# bme_affect_sen_brd.net
KiCad netlist of a schematic drawn in Altium Designer
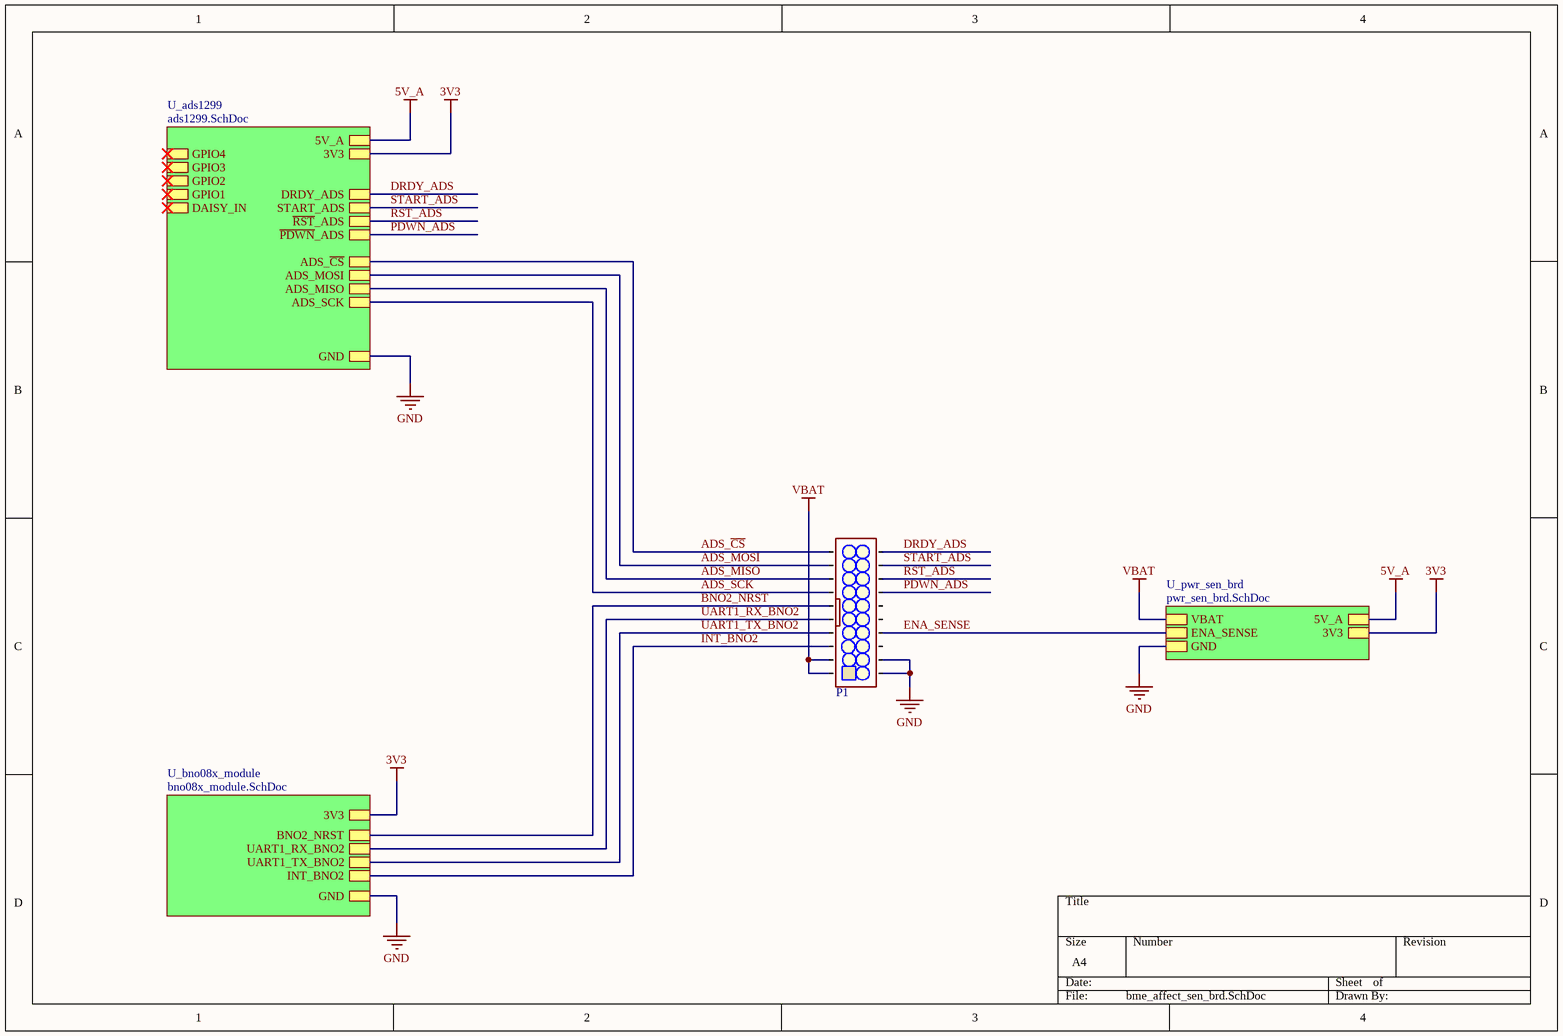
[diagram p0: bme_affect_sen_brd.SchDoc]

(export (version "E")
  (design (tool "Eeschema 10.0.6"))
  (components
    (comp (ref "P1")
      (value "2x10 Ribbon Header")
      (footprint "2x10_RIBBON_CABLE_CON")
      (description "2.54 mm")
      (fields (field (name "MANUFACTURER PART NO") "302-S201"))
      (libsource (lib "jclib") (part "2x10 Ribbon Header"))
    )
  )
  (nets
    (net (code "1") (name "/ADS_MISO") (class "Default")
      (node (ref "P1") (pin "8") (pinfunction "8_8") (pintype "passive"))
    )
    (net (code "2") (name "/ADS_MOSI") (class "Default")
      (node (ref "P1") (pin "9") (pinfunction "9_9") (pintype "passive"))
    )
    (net (code "3") (name "/ADS_SCK") (class "Default")
      (node (ref "P1") (pin "7") (pinfunction "7_7") (pintype "passive"))
    )
    (net (code "4") (name "/ADS_~{CS}") (class "Default")
      (node (ref "P1") (pin "10") (pinfunction "10_10") (pintype "passive"))
    )
    (net (code "5") (name "/BNO2_NRST") (class "Default")
      (node (ref "P1") (pin "6") (pinfunction "6_6") (pintype "passive"))
    )
    (net (code "7") (name "/DRDY_ADS") (class "Default")
      (node (ref "P1") (pin "11") (pinfunction "11_11") (pintype "passive"))
    )
    (net (code "8") (name "/ENA_SENSE") (class "Default")
      (node (ref "P1") (pin "17") (pinfunction "17_17") (pintype "passive"))
    )
    (net (code "13") (name "/INT_BNO2") (class "Default")
      (node (ref "P1") (pin "3") (pinfunction "3_3") (pintype "passive"))
    )
    (net (code "14") (name "/START_ADS") (class "Default")
      (node (ref "P1") (pin "12") (pinfunction "12_12") (pintype "passive"))
    )
    (net (code "15") (name "/UART1_RX_BNO2") (class "Default")
      (node (ref "P1") (pin "5") (pinfunction "5_5") (pintype "passive"))
    )
    (net (code "16") (name "/UART1_TX_BNO2") (class "Default")
      (node (ref "P1") (pin "4") (pinfunction "4_4") (pintype "passive"))
    )
    (net (code "17") (name "/~{PDWN}_ADS") (class "Default")
      (node (ref "P1") (pin "14") (pinfunction "14_14") (pintype "passive"))
    )
    (net (code "18") (name "/~{RST}_ADS") (class "Default")
      (node (ref "P1") (pin "13") (pinfunction "13_13") (pintype "passive"))
    )
    (net (code "21") (name "GND") (class "Default")
      (node (ref "P1") (pin "19") (pinfunction "19_19") (pintype "passive"))
      (node (ref "P1") (pin "20") (pinfunction "20_20") (pintype "passive"))
    )
    (net (code "22") (name "VBAT") (class "Default")
      (node (ref "P1") (pin "1") (pinfunction "1_1") (pintype "passive"))
      (node (ref "P1") (pin "2") (pinfunction "2_2") (pintype "passive"))
    )
    (net (code "23") (name "unconnected-(P1-Pad15)") (class "Default")
      (node (ref "P1") (pin "15") (pinfunction "15_15") (pintype "passive"))
    )
    (net (code "24") (name "unconnected-(P1-Pad16)") (class "Default")
      (node (ref "P1") (pin "16") (pinfunction "16_16") (pintype "passive"))
    )
    (net (code "25") (name "unconnected-(P1-Pad18)") (class "Default")
      (node (ref "P1") (pin "18") (pinfunction "18_18") (pintype "passive"))
    )
  )
)
